# SimpleEMGCircuit.net
KiCad netlist of a schematic drawn in EAGLE
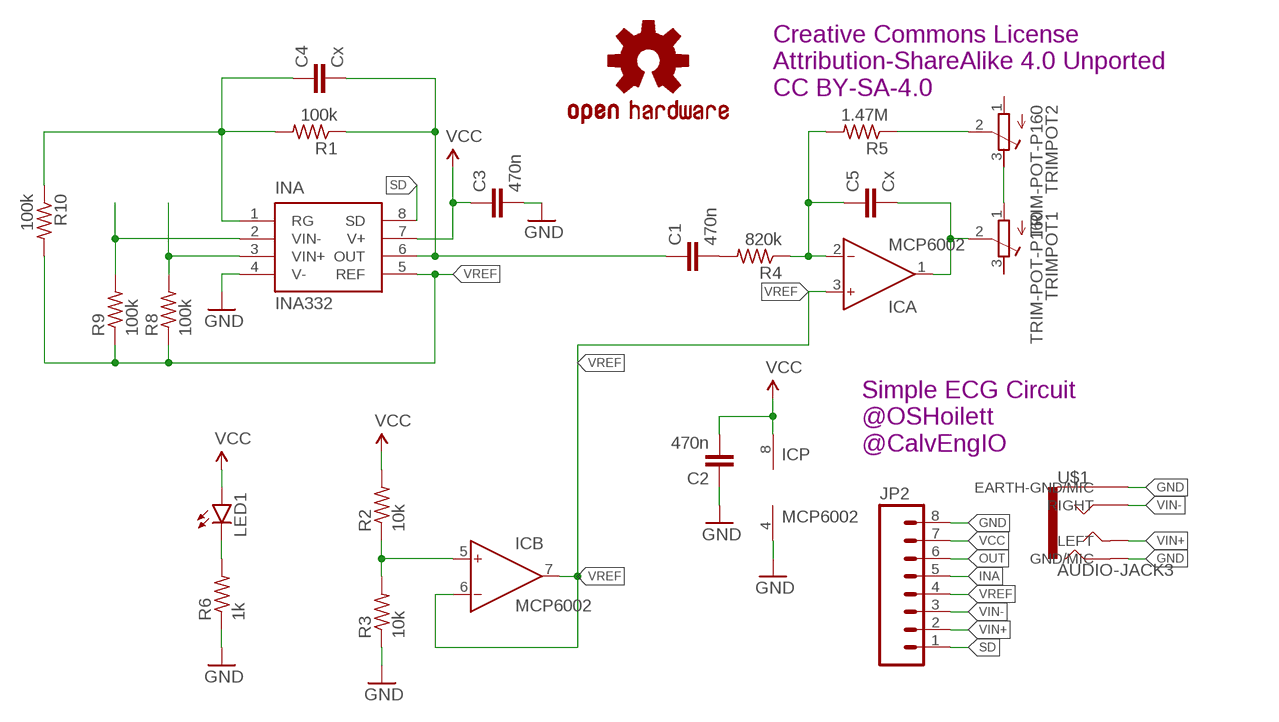
[diagram p0: schematic, sheet 1]

(export (version "E")
  (design (tool "Eeschema 10.0.6"))
  (components
    (comp (ref "C1")
      (value "470n")
      (footprint "eagle-import:C0402")
      (libsource (lib "eagle-import") (part "C-EUC0402"))
    )
    (comp (ref "C2")
      (value "470n")
      (footprint "eagle-import:C0402")
      (libsource (lib "eagle-import") (part "C-EUC0402"))
    )
    (comp (ref "C3")
      (value "470n")
      (footprint "eagle-import:C0402")
      (libsource (lib "eagle-import") (part "C-EUC0402"))
    )
    (comp (ref "C4")
      (value "Cx")
      (footprint "eagle-import:C0402")
      (libsource (lib "eagle-import") (part "C-EUC0402"))
    )
    (comp (ref "C5")
      (value "Cx")
      (footprint "eagle-import:C0402")
      (libsource (lib "eagle-import") (part "C-EUC0402"))
    )
    (comp (ref "IC")
      (value "MCP6002")
      (footprint "eagle-import:MSOP08")
      (fields (field (name "MF") "ALTERA CORPORATION") (field (name "MPN") "AD8607ARMZ-REEL"))
      (libsource (lib "eagle-import") (part "AD8607RM"))
    )
    (comp (ref "INA")
      (value "INA332")
      (footprint "eagle-import:MSOP08")
      (libsource (lib "eagle-import") (part "INA332"))
    )
    (comp (ref "JP2")
      (value "M08NO_SILK_FEMALE_PTH")
      (footprint "eagle-import:1X08_NO_SILK")
      (libsource (lib "eagle-import") (part "M08NO_SILK_FEMALE_PTH"))
    )
    (comp (ref "LED1")
      (value "LED0603")
      (footprint "eagle-import:LED-0603")
      (libsource (lib "eagle-import") (part "LED0603"))
    )
    (comp (ref "LOGO1")
      (value "OSHW-LOGOS")
      (footprint "eagle-import:OSHW-LOGO-S")
      (libsource (lib "eagle-import") (part "OSHW-LOGOS"))
    )
    (comp (ref "R1")
      (value "100k")
      (footprint "eagle-import:R0402")
      (libsource (lib "eagle-import") (part "R-US_R0402"))
    )
    (comp (ref "R2")
      (value "10k")
      (footprint "eagle-import:R0402")
      (libsource (lib "eagle-import") (part "R-US_R0402"))
    )
    (comp (ref "R3")
      (value "10k")
      (footprint "eagle-import:R0402")
      (libsource (lib "eagle-import") (part "R-US_R0402"))
    )
    (comp (ref "R4")
      (value "820k")
      (footprint "eagle-import:R0402")
      (libsource (lib "eagle-import") (part "R-US_R0402"))
    )
    (comp (ref "R5")
      (value "1.47M")
      (footprint "eagle-import:R0402")
      (libsource (lib "eagle-import") (part "R-US_R0402"))
    )
    (comp (ref "R6")
      (value "1k")
      (footprint "eagle-import:R0402")
      (libsource (lib "eagle-import") (part "R-US_R0402"))
    )
    (comp (ref "R8")
      (value "100k")
      (footprint "eagle-import:R0402")
      (libsource (lib "eagle-import") (part "R-US_R0402"))
    )
    (comp (ref "R9")
      (value "100k")
      (footprint "eagle-import:R0402")
      (libsource (lib "eagle-import") (part "R-US_R0402"))
    )
    (comp (ref "R10")
      (value "100k")
      (footprint "eagle-import:R0402")
      (libsource (lib "eagle-import") (part "R-US_R0402"))
    )
    (comp (ref "TRIMPOT1")
      (value "TRIM-POT-P160")
      (footprint "eagle-import:16MMROTARYPOT")
      (libsource (lib "eagle-import") (part "TRIM-POT-P160"))
    )
    (comp (ref "TRIMPOT2")
      (value "TRIM-POT-P160")
      (footprint "eagle-import:16MMROTARYPOT")
      (libsource (lib "eagle-import") (part "TRIM-POT-P160"))
    )
    (comp (ref "U$1")
      (value "AUDIO-JACK3")
      (footprint "eagle-import:AUDIO-JACK-TRRS-SMD")
      (libsource (lib "eagle-import") (part "AUDIO-JACK3"))
    )
  )
  (nets
    (net (code "1") (name "GND") (class "Default")
      (node (ref "C2") (pin "1") (pinfunction "1_1") (pintype "passive"))
      (node (ref "C3") (pin "2") (pinfunction "2_2") (pintype "passive"))
      (node (ref "IC") (pin "4") (pinfunction "V-_4") (pintype "power_in"))
      (node (ref "INA") (pin "4") (pinfunction "V-_4") (pintype "bidirectional"))
      (node (ref "JP2") (pin "8") (pinfunction "8_8") (pintype "passive"))
      (node (ref "R3") (pin "1") (pinfunction "1_1") (pintype "passive"))
      (node (ref "R6") (pin "1") (pinfunction "1_1") (pintype "passive"))
      (node (ref "U$1") (pin "EARTH") (pinfunction "EARTH-GND/MIC_EARTH") (pintype "bidirectional"))
      (node (ref "U$1") (pin "RING2") (pinfunction "GND/MIC_RING2") (pintype "bidirectional"))
    )
    (net (code "2") (name "INA") (class "Default")
      (node (ref "C1") (pin "1") (pinfunction "1_1") (pintype "passive"))
      (node (ref "C4") (pin "2") (pinfunction "2_2") (pintype "passive"))
      (node (ref "INA") (pin "6") (pinfunction "OUT_6") (pintype "bidirectional"))
      (node (ref "JP2") (pin "5") (pinfunction "5_5") (pintype "passive"))
      (node (ref "R1") (pin "1") (pinfunction "1_1") (pintype "passive"))
    )
    (net (code "3") (name "Net-(C1-Pad2)") (class "Default")
      (node (ref "C1") (pin "2") (pinfunction "2_2") (pintype "passive"))
      (node (ref "R4") (pin "2") (pinfunction "2_2") (pintype "passive"))
    )
    (net (code "4") (name "Net-(ICA-IN-)") (class "Default")
      (node (ref "C5") (pin "1") (pinfunction "1_1") (pintype "passive"))
      (node (ref "IC") (pin "2") (pinfunction "IN-_2") (pintype "input"))
      (node (ref "R4") (pin "1") (pinfunction "1_1") (pintype "passive"))
      (node (ref "R5") (pin "2") (pinfunction "2_2") (pintype "passive"))
    )
    (net (code "5") (name "Net-(ICB-IN+)") (class "Default")
      (node (ref "IC") (pin "5") (pinfunction "IN+_5") (pintype "input"))
      (node (ref "R2") (pin "1") (pinfunction "1_1") (pintype "passive"))
      (node (ref "R3") (pin "2") (pinfunction "2_2") (pintype "passive"))
    )
    (net (code "6") (name "Net-(INA-RG)") (class "Default")
      (node (ref "C4") (pin "1") (pinfunction "1_1") (pintype "passive"))
      (node (ref "INA") (pin "1") (pinfunction "RG_1") (pintype "bidirectional"))
      (node (ref "R1") (pin "2") (pinfunction "2_2") (pintype "passive"))
      (node (ref "R10") (pin "1") (pinfunction "1_1") (pintype "passive"))
    )
    (net (code "7") (name "Net-(LED1-PadC)") (class "Default")
      (node (ref "LED1") (pin "C") (pinfunction "C_C") (pintype "passive"))
      (node (ref "R6") (pin "2") (pinfunction "2_2") (pintype "passive"))
    )
    (net (code "8") (name "Net-(TRIMPOT1-A)") (class "Default")
      (node (ref "TRIMPOT1") (pin "1") (pinfunction "A_1") (pintype "passive"))
      (node (ref "TRIMPOT2") (pin "3") (pinfunction "E_3") (pintype "passive"))
    )
    (net (code "9") (name "Net-(TRIMPOT2-S)") (class "Default")
      (node (ref "R5") (pin "1") (pinfunction "1_1") (pintype "passive"))
      (node (ref "TRIMPOT2") (pin "2") (pinfunction "S_2") (pintype "passive"))
    )
    (net (code "10") (name "OUT") (class "Default")
      (node (ref "C5") (pin "2") (pinfunction "2_2") (pintype "passive"))
      (node (ref "IC") (pin "1") (pinfunction "OUT_1") (pintype "output"))
      (node (ref "JP2") (pin "6") (pinfunction "6_6") (pintype "passive"))
      (node (ref "TRIMPOT1") (pin "2") (pinfunction "S_2") (pintype "passive"))
    )
    (net (code "11") (name "SD") (class "Default")
      (node (ref "INA") (pin "8") (pinfunction "SD_8") (pintype "bidirectional"))
      (node (ref "JP2") (pin "1") (pinfunction "1_1") (pintype "passive"))
    )
    (net (code "12") (name "VCC") (class "Default")
      (node (ref "C2") (pin "2") (pinfunction "2_2") (pintype "passive"))
      (node (ref "C3") (pin "1") (pinfunction "1_1") (pintype "passive"))
      (node (ref "IC") (pin "8") (pinfunction "V+_8") (pintype "power_in"))
      (node (ref "INA") (pin "7") (pinfunction "V+_7") (pintype "bidirectional"))
      (node (ref "JP2") (pin "7") (pinfunction "7_7") (pintype "passive"))
      (node (ref "LED1") (pin "A") (pinfunction "A_A") (pintype "passive"))
      (node (ref "R2") (pin "2") (pinfunction "2_2") (pintype "passive"))
    )
    (net (code "13") (name "VIN+") (class "Default")
      (node (ref "INA") (pin "3") (pinfunction "VIN+_3") (pintype "bidirectional"))
      (node (ref "JP2") (pin "2") (pinfunction "2_2") (pintype "passive"))
      (node (ref "R8") (pin "2") (pinfunction "2_2") (pintype "passive"))
      (node (ref "U$1") (pin "TIP") (pinfunction "LEFT_TIP") (pintype "bidirectional"))
    )
    (net (code "14") (name "VIN-") (class "Default")
      (node (ref "INA") (pin "2") (pinfunction "VIN-_2") (pintype "bidirectional"))
      (node (ref "JP2") (pin "3") (pinfunction "3_3") (pintype "passive"))
      (node (ref "R9") (pin "2") (pinfunction "2_2") (pintype "passive"))
      (node (ref "U$1") (pin "RING1") (pinfunction "RIGHT_RING1") (pintype "bidirectional"))
    )
    (net (code "15") (name "VREF") (class "Default")
      (node (ref "IC") (pin "3") (pinfunction "IN+_3") (pintype "input"))
      (node (ref "IC") (pin "6") (pinfunction "IN-_6") (pintype "input"))
      (node (ref "IC") (pin "7") (pinfunction "OUT_7") (pintype "output"))
      (node (ref "INA") (pin "5") (pinfunction "REF_5") (pintype "bidirectional"))
      (node (ref "JP2") (pin "4") (pinfunction "4_4") (pintype "passive"))
      (node (ref "R10") (pin "2") (pinfunction "2_2") (pintype "passive"))
      (node (ref "R8") (pin "1") (pinfunction "1_1") (pintype "passive"))
      (node (ref "R9") (pin "1") (pinfunction "1_1") (pintype "passive"))
    )
    (net (code "16") (name "unconnected-(TRIMPOT1-E-Pad3)") (class "Default")
      (node (ref "TRIMPOT1") (pin "3") (pinfunction "E_3") (pintype "passive"))
    )
    (net (code "17") (name "unconnected-(TRIMPOT2-A-Pad1)") (class "Default")
      (node (ref "TRIMPOT2") (pin "1") (pinfunction "A_1") (pintype "passive"))
    )
  )
)
